# boxer_supply.net
KiCad netlist of a schematic drawn in Altium Designer
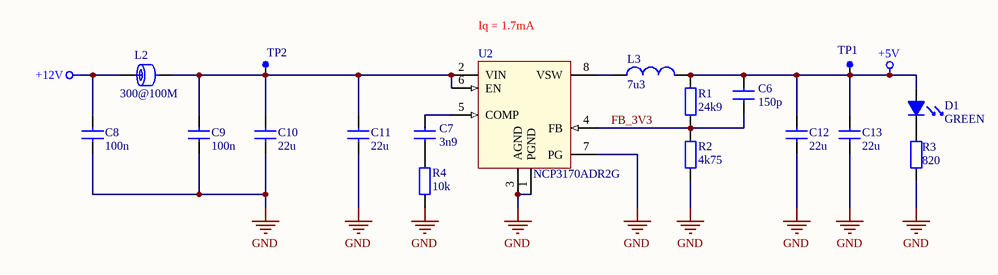
[diagram p0: boxer_supply.SchDoc]

(export (version "E")
  (design (tool "Eeschema 10.0.6"))
  (components
    (comp (ref "C6")
      (value "150p")
      (footprint "C_0805")
      (description "Capacitor")
      (fields (field (name "Comment") "885012207081"))
      (libsource (lib "boxer_pas") (part "Capacitor"))
    )
    (comp (ref "C7")
      (value "3n9")
      (footprint "C_0805")
      (description "Capacitor")
      (fields (field (name "Comment") "885012207089"))
      (libsource (lib "boxer_pas") (part "Capacitor"))
    )
    (comp (ref "C8")
      (value "100n")
      (footprint "C_0805")
      (description "Capacitor")
      (libsource (lib "boxer_pas") (part "Capacitor"))
    )
    (comp (ref "C9")
      (value "100n")
      (footprint "C_0805")
      (description "Capacitor")
      (libsource (lib "boxer_pas") (part "Capacitor"))
    )
    (comp (ref "C10")
      (value "22u")
      (footprint "C_1206")
      (description "Capacitor")
      (fields (field (name "Comment") "TME: CL31A226MOCLNNC"))
      (libsource (lib "boxer_pas") (part "Capacitor"))
    )
    (comp (ref "C11")
      (value "22u")
      (footprint "C_1206")
      (description "Capacitor")
      (fields (field (name "Comment") "TME: CL31A226MOCLNNC"))
      (libsource (lib "boxer_pas") (part "Capacitor"))
    )
    (comp (ref "C12")
      (value "22u")
      (footprint "C_1206")
      (description "Capacitor")
      (fields (field (name "Comment") "TME: CL31A226MOCLNNC"))
      (libsource (lib "boxer_pas") (part "Capacitor"))
    )
    (comp (ref "C13")
      (value "22u")
      (footprint "C_1206")
      (description "Capacitor")
      (fields (field (name "Comment") "TME: CL31A226MOCLNNC"))
      (libsource (lib "boxer_pas") (part "Capacitor"))
    )
    (comp (ref "D1")
      (value "GREEN")
      (footprint "LED_0805")
      (description "Typical RED, GREEN, YELLOW, AMBER GaAs LED")
      (fields (field (name "Comment") "KP-2012LSGC"))
      (libsource (lib "altium-import") (part "root_3_LED_"))
    )
    (comp (ref "L2")
      (value "300@100M")
      (footprint "L_0805")
      (description "Ferrite Bead")
      (fields (field (name "Comment") "742792031"))
      (libsource (lib "boxer_pas") (part "FB"))
    )
    (comp (ref "L3")
      (value "7u3")
      (footprint "L_6.7x6.7mm")
      (description "FIXED IND 7.3UH 2.1A 54 MOHM SMD")
      (fields (field (name "Comment") "308-1500-1-ND"))
      (libsource (lib "boxer_pas") (part "Inductor"))
    )
    (comp (ref "R1")
      (value "24k9")
      (footprint "R_0805")
      (description "Resistor")
      (fields (field (name "Comment") "RNCP0805FTD24K9"))
      (libsource (lib "boxer_pas") (part "Resistor"))
    )
    (comp (ref "R2")
      (value "4k75")
      (footprint "R_0805")
      (description "Resistor")
      (fields (field (name "Comment") "RNCP0805FTD4K75"))
      (libsource (lib "boxer_pas") (part "Resistor"))
    )
    (comp (ref "R3")
      (value "820")
      (footprint "R_0805")
      (description "Resistor")
      (libsource (lib "altium-import") (part "root_1_Resistor_"))
    )
    (comp (ref "R4")
      (value "10k")
      (footprint "R_1206")
      (description "Resistor")
      (libsource (lib "boxer_pas") (part "Resistor"))
    )
    (comp (ref "TP1")
      (value "TEST PAD")
      (footprint "PIN")
      (description "PAD 1.5mm")
      (libsource (lib "boxer_mechanical") (part "TEST_PAD"))
    )
    (comp (ref "TP2")
      (value "TEST PAD")
      (footprint "PIN")
      (description "PAD 1.5mm")
      (libsource (lib "boxer_mechanical") (part "TEST_PAD"))
    )
    (comp (ref "U2")
      (value "NCP3170ADR2G")
      (footprint "SO8")
      (description "Synchronous PWM Switching Converter")
      (libsource (lib "boxer_ic") (part "NCP3170"))
    )
  )
  (nets
    (net (code "1") (name "+5V") (class "Default")
      (node (ref "C12") (pin "2") (pinfunction "2_2") (pintype "passive"))
      (node (ref "C13") (pin "2") (pinfunction "2_2") (pintype "passive"))
      (node (ref "C6") (pin "2") (pinfunction "2_2") (pintype "passive"))
      (node (ref "D1") (pin "1") (pinfunction "A_1") (pintype "passive"))
      (node (ref "L3") (pin "2") (pinfunction "2_2") (pintype "passive"))
      (node (ref "R1") (pin "2") (pinfunction "2_2") (pintype "passive"))
      (node (ref "TP1") (pin "1") (pinfunction "1_1") (pintype "passive"))
    )
    (net (code "2") (name "+12V") (class "Default")
      (node (ref "C8") (pin "2") (pinfunction "2_2") (pintype "passive"))
      (node (ref "L2") (pin "1") (pinfunction "1_1") (pintype "passive"))
    )
    (net (code "3") (name "/FB_3V3") (class "Default")
      (node (ref "C6") (pin "1") (pinfunction "1_1") (pintype "passive"))
      (node (ref "R1") (pin "1") (pinfunction "1_1") (pintype "passive"))
      (node (ref "R2") (pin "2") (pinfunction "2_2") (pintype "passive"))
      (node (ref "U2") (pin "4") (pinfunction "FB_4") (pintype "input"))
    )
    (net (code "4") (name "GND") (class "Default")
      (node (ref "C10") (pin "1") (pinfunction "1_1") (pintype "passive"))
      (node (ref "C11") (pin "1") (pinfunction "1_1") (pintype "passive"))
      (node (ref "C12") (pin "1") (pinfunction "1_1") (pintype "passive"))
      (node (ref "C13") (pin "1") (pinfunction "1_1") (pintype "passive"))
      (node (ref "C8") (pin "1") (pinfunction "1_1") (pintype "passive"))
      (node (ref "C9") (pin "1") (pinfunction "1_1") (pintype "passive"))
      (node (ref "R2") (pin "1") (pinfunction "1_1") (pintype "passive"))
      (node (ref "R3") (pin "1") (pinfunction "1_1") (pintype "passive"))
      (node (ref "R4") (pin "1") (pinfunction "1_1") (pintype "passive"))
      (node (ref "U2") (pin "1") (pinfunction "PGND_1") (pintype "power_in"))
      (node (ref "U2") (pin "3") (pinfunction "AGND_3") (pintype "power_in"))
      (node (ref "U2") (pin "7") (pinfunction "PG_7") (pintype "passive"))
    )
    (net (code "5") (name "Net-(C7-Pad1)") (class "Default")
      (node (ref "C7") (pin "1") (pinfunction "1_1") (pintype "passive"))
      (node (ref "R4") (pin "2") (pinfunction "2_2") (pintype "passive"))
    )
    (net (code "6") (name "Net-(D1-K)") (class "Default")
      (node (ref "D1") (pin "2") (pinfunction "K_2") (pintype "passive"))
      (node (ref "R3") (pin "2") (pinfunction "2_2") (pintype "passive"))
    )
    (net (code "7") (name "Net-(U2-COMP)") (class "Default")
      (node (ref "C7") (pin "2") (pinfunction "2_2") (pintype "passive"))
      (node (ref "U2") (pin "5") (pinfunction "COMP_5") (pintype "input"))
    )
    (net (code "8") (name "Net-(U2-EN)") (class "Default")
      (node (ref "C10") (pin "2") (pinfunction "2_2") (pintype "passive"))
      (node (ref "C11") (pin "2") (pinfunction "2_2") (pintype "passive"))
      (node (ref "C9") (pin "2") (pinfunction "2_2") (pintype "passive"))
      (node (ref "L2") (pin "2") (pinfunction "2_2") (pintype "passive"))
      (node (ref "TP2") (pin "1") (pinfunction "1_1") (pintype "passive"))
      (node (ref "U2") (pin "2") (pinfunction "VIN_2") (pintype "power_in"))
      (node (ref "U2") (pin "6") (pinfunction "EN_6") (pintype "input"))
    )
    (net (code "9") (name "Net-(U2-VSW)") (class "Default")
      (node (ref "L3") (pin "1") (pinfunction "1_1") (pintype "passive"))
      (node (ref "U2") (pin "8") (pinfunction "VSW_8") (pintype "power_in"))
    )
  )
)
